# NIRGM_V5.net
KiCad netlist of a schematic drawn in EAGLE
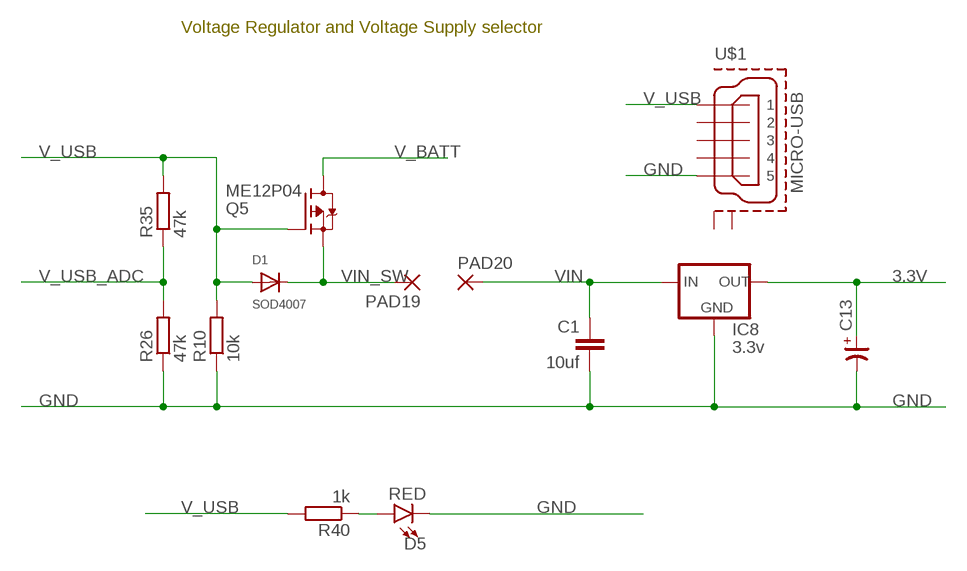
[diagram p0: schematic, sheet 1]
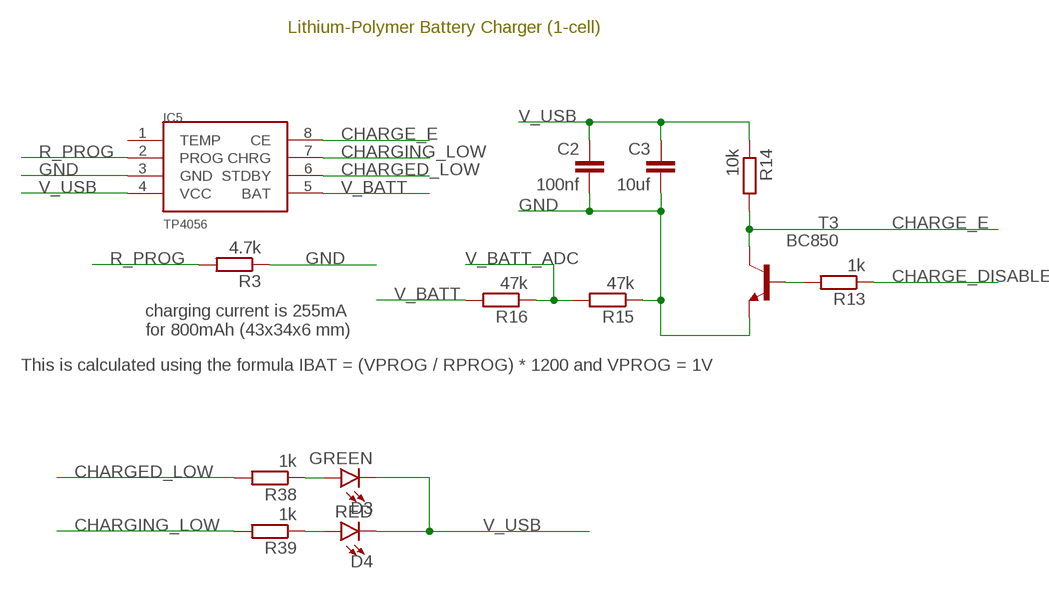
[diagram p1: schematic, sheet 2]
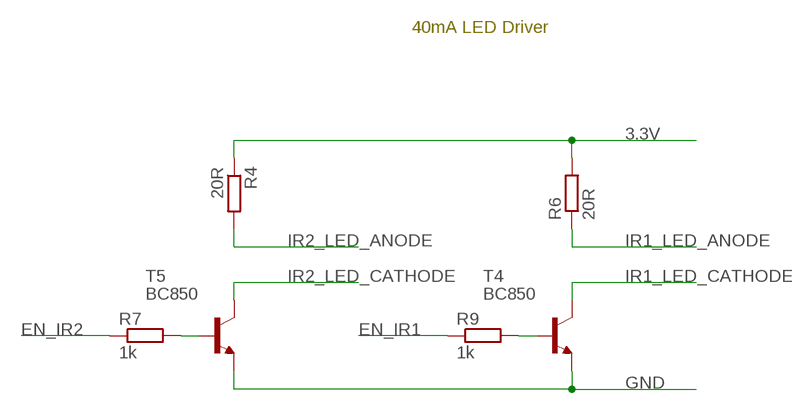
[diagram p2: schematic, sheet 3]
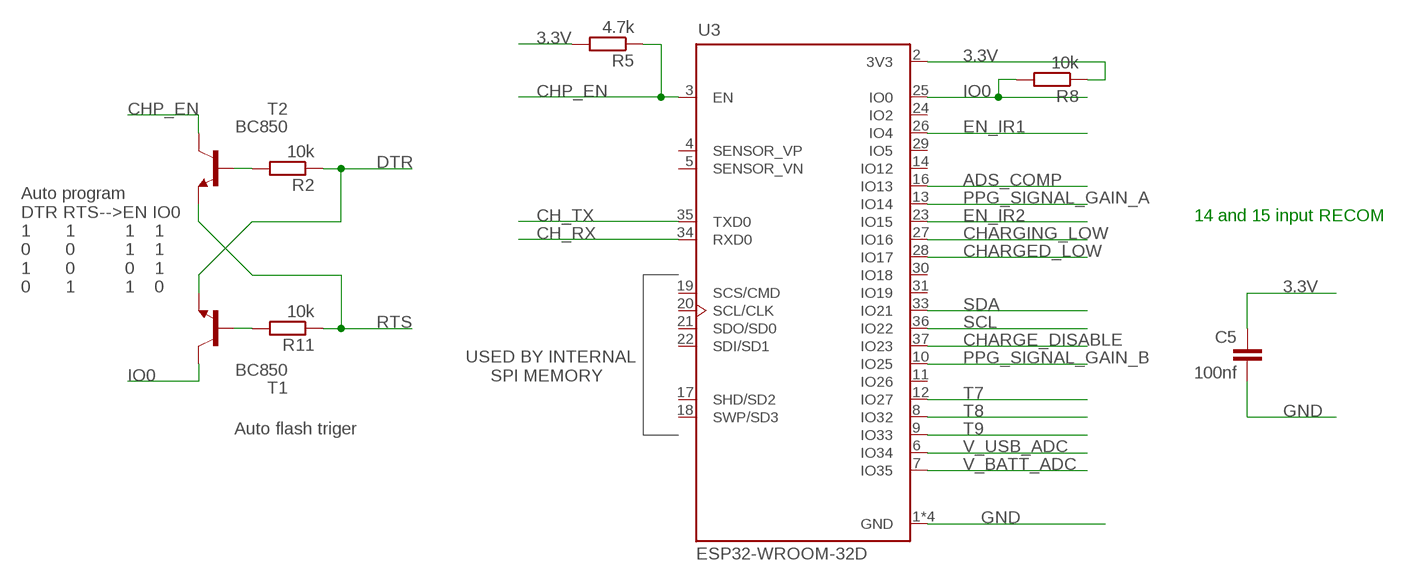
[diagram p3: schematic, sheet 4]
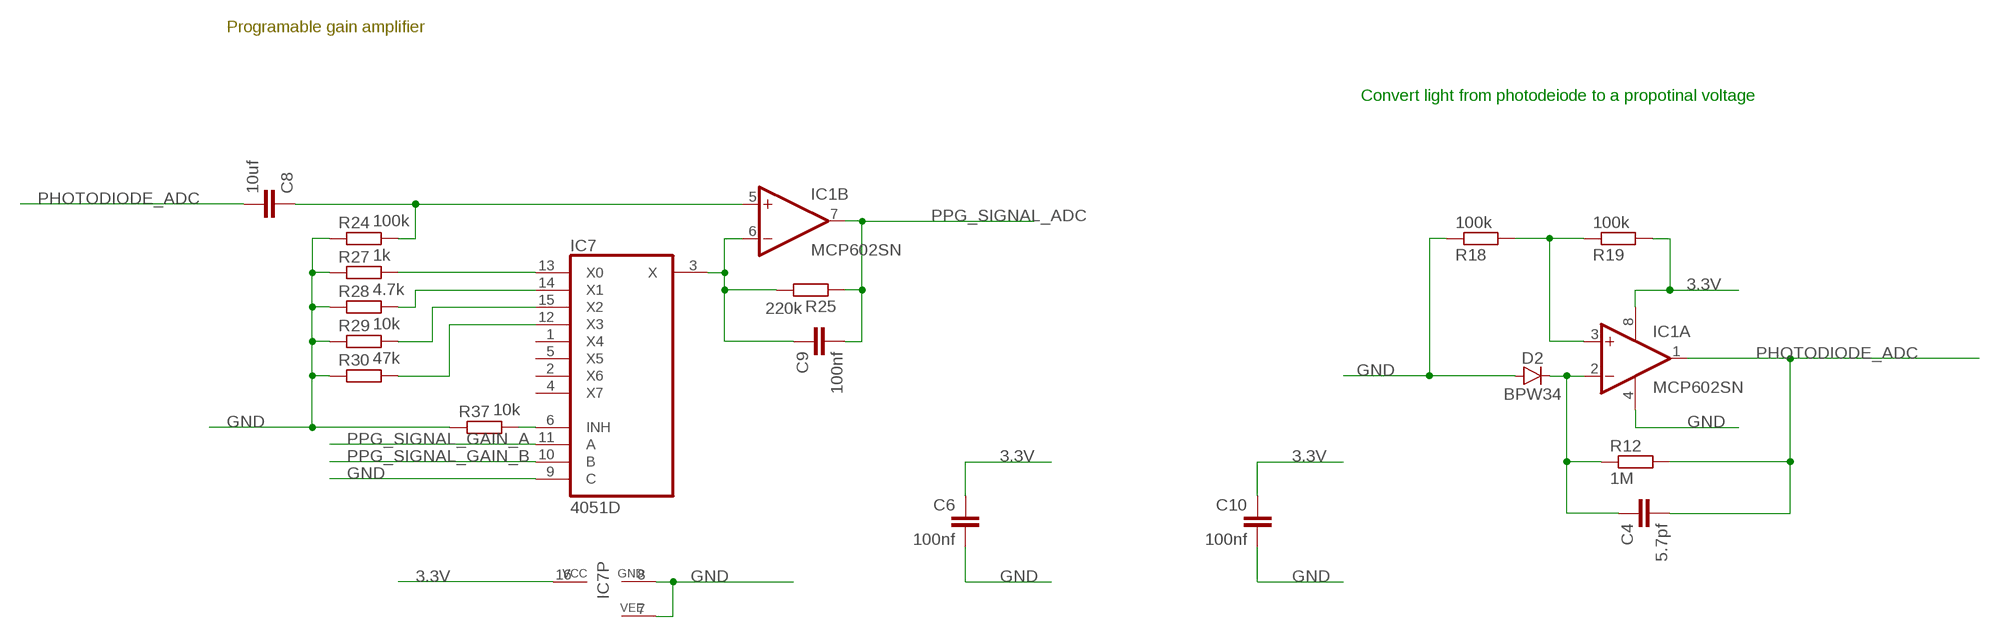
[diagram p4: schematic, sheet 5]
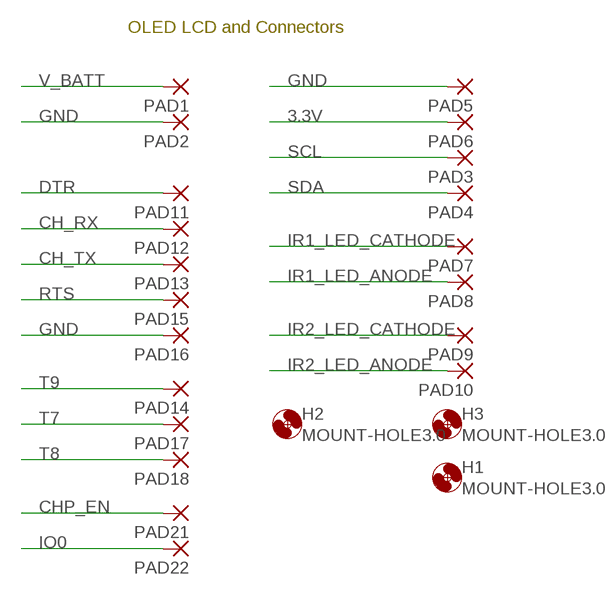
[diagram p5: schematic, sheet 6]
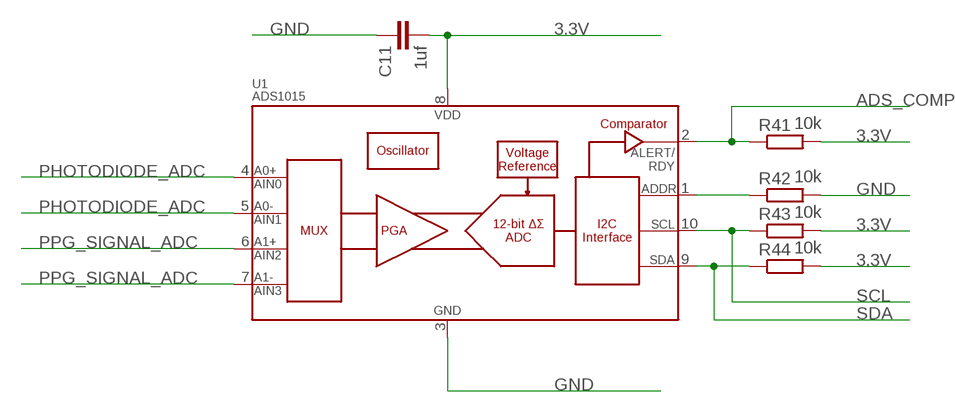
[diagram p6: schematic, sheet 7]

(export (version "E")
  (design (tool "Eeschema 10.0.6"))
  (components
    (comp (ref "C5")
      (value "100nf")
      (footprint "eagle-import:C1206K")
      (libsource (lib "eagle-import") (part "C-EUC1206K"))
    )
    (comp (ref "R2")
      (value "10k")
      (footprint "eagle-import:R1206")
      (libsource (lib "eagle-import") (part "R-EU_R1206"))
    )
    (comp (ref "R5")
      (value "4.7k")
      (footprint "eagle-import:R1206")
      (libsource (lib "eagle-import") (part "R-EU_R1206"))
    )
    (comp (ref "R8")
      (value "10k")
      (footprint "eagle-import:R1206")
      (libsource (lib "eagle-import") (part "R-EU_R1206"))
    )
    (comp (ref "R11")
      (value "10k")
      (footprint "eagle-import:R1206")
      (libsource (lib "eagle-import") (part "R-EU_R1206"))
    )
    (comp (ref "T1")
      (value "BC850")
      (footprint "eagle-import:SOT23")
      (libsource (lib "eagle-import") (part "BC850"))
    )
    (comp (ref "T2")
      (value "BC850")
      (footprint "eagle-import:SOT23")
      (libsource (lib "eagle-import") (part "BC850"))
    )
    (comp (ref "U3")
      (value "ESP32-WROOM-32D")
      (footprint "eagle-import:MODULE_ESP32-WROOM-32D")
      (fields (field (name "MF") "Espressif Systems"))
      (libsource (lib "eagle-import") (part "ESP32-WROOM-32D"))
    )
    (comp (ref "C11")
      (value "1uf")
      (footprint "eagle-import:C1206K")
      (libsource (lib "eagle-import") (part "C-EUC1206K"))
    )
    (comp (ref "R41")
      (value "10k")
      (footprint "eagle-import:R1206")
      (libsource (lib "eagle-import") (part "R-EU_R1206"))
    )
    (comp (ref "R42")
      (value "10k")
      (footprint "eagle-import:R1206")
      (libsource (lib "eagle-import") (part "R-EU_R1206"))
    )
    (comp (ref "R43")
      (value "10k")
      (footprint "eagle-import:R1206")
      (libsource (lib "eagle-import") (part "R-EU_R1206"))
    )
    (comp (ref "R44")
      (value "10k")
      (footprint "eagle-import:R1206")
      (libsource (lib "eagle-import") (part "R-EU_R1206"))
    )
    (comp (ref "U1")
      (value "ADS1015")
      (footprint "eagle-import:MSOP10")
      (libsource (lib "eagle-import") (part "ADS1015"))
    )
    (comp (ref "C2")
      (value "100nf")
      (footprint "eagle-import:C1206K")
      (libsource (lib "eagle-import") (part "C-EUC1206K"))
    )
    (comp (ref "C3")
      (value "10uf")
      (footprint "eagle-import:C1206K")
      (libsource (lib "eagle-import") (part "C-EUC1206K"))
    )
    (comp (ref "D3")
      (value "GREEN")
      (footprint "eagle-import:LED-1206")
      (libsource (lib "eagle-import") (part "LED-GREEN1206"))
    )
    (comp (ref "D4")
      (value "RED")
      (footprint "eagle-import:LED-1206")
      (libsource (lib "eagle-import") (part "LED-GREEN1206"))
    )
    (comp (ref "IC5")
      (value "TP4056")
      (footprint "eagle-import:SOP-8")
      (libsource (lib "eagle-import") (part "TP4056"))
    )
    (comp (ref "R3")
      (value "4.7k")
      (footprint "eagle-import:R1206")
      (libsource (lib "eagle-import") (part "R-EU_R1206"))
    )
    (comp (ref "R13")
      (value "1k")
      (footprint "eagle-import:R1206")
      (libsource (lib "eagle-import") (part "R-EU_R1206"))
    )
    (comp (ref "R14")
      (value "10k")
      (footprint "eagle-import:R1206")
      (libsource (lib "eagle-import") (part "R-EU_R1206"))
    )
    (comp (ref "R15")
      (value "47k")
      (footprint "eagle-import:R1206")
      (libsource (lib "eagle-import") (part "R-EU_R1206"))
    )
    (comp (ref "R16")
      (value "47k")
      (footprint "eagle-import:R1206")
      (libsource (lib "eagle-import") (part "R-EU_R1206"))
    )
    (comp (ref "R38")
      (value "1k")
      (footprint "eagle-import:R1206")
      (libsource (lib "eagle-import") (part "R-EU_R1206"))
    )
    (comp (ref "R39")
      (value "1k")
      (footprint "eagle-import:R1206")
      (libsource (lib "eagle-import") (part "R-EU_R1206"))
    )
    (comp (ref "T3")
      (value "BC850")
      (footprint "eagle-import:SOT23")
      (libsource (lib "eagle-import") (part "BC850"))
    )
    (comp (ref "R4")
      (value "20R")
      (footprint "eagle-import:R1206")
      (libsource (lib "eagle-import") (part "R-EU_R1206"))
    )
    (comp (ref "R6")
      (value "20R")
      (footprint "eagle-import:R1206")
      (libsource (lib "eagle-import") (part "R-EU_R1206"))
    )
    (comp (ref "R7")
      (value "1k")
      (footprint "eagle-import:R1206")
      (libsource (lib "eagle-import") (part "R-EU_R1206"))
    )
    (comp (ref "R9")
      (value "1k")
      (footprint "eagle-import:R1206")
      (libsource (lib "eagle-import") (part "R-EU_R1206"))
    )
    (comp (ref "T4")
      (value "BC850")
      (footprint "eagle-import:SOT23")
      (libsource (lib "eagle-import") (part "BC850"))
    )
    (comp (ref "T5")
      (value "BC850")
      (footprint "eagle-import:SOT23")
      (libsource (lib "eagle-import") (part "BC850"))
    )
    (comp (ref "C1")
      (value "10uf")
      (footprint "eagle-import:C1206K")
      (libsource (lib "eagle-import") (part "C-EUC1206K"))
    )
    (comp (ref "C13")
      (value "CP-7343")
      (footprint "eagle-import:7343_T")
      (libsource (lib "eagle-import") (part "CP-7343"))
    )
    (comp (ref "D1")
      (value "SOD4007")
      (footprint "eagle-import:SOD-123FL")
      (libsource (lib "eagle-import") (part "DIODE_SOD-123FL"))
    )
    (comp (ref "D5")
      (value "RED")
      (footprint "eagle-import:LED-1206")
      (libsource (lib "eagle-import") (part "LED-GREEN1206"))
    )
    (comp (ref "IC8")
      (value "3.3v")
      (footprint "eagle-import:TO252")
      (libsource (lib "eagle-import") (part "LM1117TO252"))
    )
    (comp (ref "PAD19")
      (value "SMD2")
      (footprint "eagle-import:SMD1,27-2,54")
      (libsource (lib "eagle-import") (part "SMD2"))
    )
    (comp (ref "PAD20")
      (value "SMD2")
      (footprint "eagle-import:SMD1,27-2,54")
      (libsource (lib "eagle-import") (part "SMD2"))
    )
    (comp (ref "Q5")
      (value "ME12P04")
      (footprint "eagle-import:TO252")
      (libsource (lib "eagle-import") (part "FDD4141TO252"))
    )
    (comp (ref "R10")
      (value "10k")
      (footprint "eagle-import:R1206")
      (libsource (lib "eagle-import") (part "R-EU_R1206"))
    )
    (comp (ref "R26")
      (value "47k")
      (footprint "eagle-import:R1206")
      (libsource (lib "eagle-import") (part "R-EU_R1206"))
    )
    (comp (ref "R35")
      (value "47k")
      (footprint "eagle-import:R1206")
      (libsource (lib "eagle-import") (part "R-EU_R1206"))
    )
    (comp (ref "R40")
      (value "1k")
      (footprint "eagle-import:R1206")
      (libsource (lib "eagle-import") (part "R-EU_R1206"))
    )
    (comp (ref "U$1")
      (value "MICRO-USB")
      (footprint "eagle-import:47589-0001")
      (libsource (lib "eagle-import") (part "MICRO-USB-RECEPTACLE47589-0001"))
    )
    (comp (ref "H1")
      (value "MOUNT-HOLE3.0")
      (footprint "eagle-import:3,0")
      (libsource (lib "eagle-import") (part "MOUNT-HOLE3.0"))
    )
    (comp (ref "H2")
      (value "MOUNT-HOLE3.0")
      (footprint "eagle-import:3,0")
      (libsource (lib "eagle-import") (part "MOUNT-HOLE3.0"))
    )
    (comp (ref "H3")
      (value "MOUNT-HOLE3.0")
      (footprint "eagle-import:3,0")
      (libsource (lib "eagle-import") (part "MOUNT-HOLE3.0"))
    )
    (comp (ref "PAD1")
      (value "WIREPADSMD5-2,5")
      (footprint "eagle-import:5-2,5")
      (libsource (lib "eagle-import") (part "WIREPADSMD5-2,5"))
    )
    (comp (ref "PAD2")
      (value "WIREPADSMD5-2,5")
      (footprint "eagle-import:5-2,5")
      (libsource (lib "eagle-import") (part "WIREPADSMD5-2,5"))
    )
    (comp (ref "PAD3")
      (value "SMD2")
      (footprint "eagle-import:SMD1,27-2,54")
      (libsource (lib "eagle-import") (part "SMD2"))
    )
    (comp (ref "PAD4")
      (value "SMD2")
      (footprint "eagle-import:SMD1,27-2,54")
      (libsource (lib "eagle-import") (part "SMD2"))
    )
    (comp (ref "PAD5")
      (value "SMD2")
      (footprint "eagle-import:SMD1,27-2,54")
      (libsource (lib "eagle-import") (part "SMD2"))
    )
    (comp (ref "PAD6")
      (value "SMD2")
      (footprint "eagle-import:SMD1,27-2,54")
      (libsource (lib "eagle-import") (part "SMD2"))
    )
    (comp (ref "PAD7")
      (value "SMD2")
      (footprint "eagle-import:SMD1,27-2,54")
      (libsource (lib "eagle-import") (part "SMD2"))
    )
    (comp (ref "PAD8")
      (value "SMD2")
      (footprint "eagle-import:SMD1,27-2,54")
      (libsource (lib "eagle-import") (part "SMD2"))
    )
    (comp (ref "PAD9")
      (value "SMD2")
      (footprint "eagle-import:SMD1,27-2,54")
      (libsource (lib "eagle-import") (part "SMD2"))
    )
    (comp (ref "PAD10")
      (value "SMD2")
      (footprint "eagle-import:SMD1,27-2,54")
      (libsource (lib "eagle-import") (part "SMD2"))
    )
    (comp (ref "PAD11")
      (value "SMD2")
      (footprint "eagle-import:SMD1,27-2,54")
      (libsource (lib "eagle-import") (part "SMD2"))
    )
    (comp (ref "PAD12")
      (value "SMD2")
      (footprint "eagle-import:SMD1,27-2,54")
      (libsource (lib "eagle-import") (part "SMD2"))
    )
    (comp (ref "PAD13")
      (value "SMD2")
      (footprint "eagle-import:SMD1,27-2,54")
      (libsource (lib "eagle-import") (part "SMD2"))
    )
    (comp (ref "PAD14")
      (value "SMD2")
      (footprint "eagle-import:SMD1,27-2,54")
      (libsource (lib "eagle-import") (part "SMD2"))
    )
    (comp (ref "PAD15")
      (value "SMD2")
      (footprint "eagle-import:SMD1,27-2,54")
      (libsource (lib "eagle-import") (part "SMD2"))
    )
    (comp (ref "PAD16")
      (value "SMD2")
      (footprint "eagle-import:SMD1,27-2,54")
      (libsource (lib "eagle-import") (part "SMD2"))
    )
    (comp (ref "PAD17")
      (value "SMD2")
      (footprint "eagle-import:SMD1,27-2,54")
      (libsource (lib "eagle-import") (part "SMD2"))
    )
    (comp (ref "PAD18")
      (value "SMD2")
      (footprint "eagle-import:SMD1,27-2,54")
      (libsource (lib "eagle-import") (part "SMD2"))
    )
    (comp (ref "PAD21")
      (value "SMD2")
      (footprint "eagle-import:SMD1,27-2,54")
      (libsource (lib "eagle-import") (part "SMD2"))
    )
    (comp (ref "PAD22")
      (value "SMD2")
      (footprint "eagle-import:SMD1,27-2,54")
      (libsource (lib "eagle-import") (part "SMD2"))
    )
    (comp (ref "C4")
      (value "5.7pf")
      (footprint "eagle-import:C1206K")
      (libsource (lib "eagle-import") (part "C-EUC1206K"))
    )
    (comp (ref "C6")
      (value "100nf")
      (footprint "eagle-import:C1206K")
      (libsource (lib "eagle-import") (part "C-EUC1206K"))
    )
    (comp (ref "C8")
      (value "10uf")
      (footprint "eagle-import:C1206K")
      (libsource (lib "eagle-import") (part "C-EUC1206K"))
    )
    (comp (ref "C9")
      (value "100nf")
      (footprint "eagle-import:C1206K")
      (libsource (lib "eagle-import") (part "C-EUC1206K"))
    )
    (comp (ref "C10")
      (value "100nf")
      (footprint "eagle-import:C1206K")
      (libsource (lib "eagle-import") (part "C-EUC1206K"))
    )
    (comp (ref "D2")
      (value "BPW34")
      (footprint "eagle-import:BPW34")
      (libsource (lib "eagle-import") (part "BPW34"))
    )
    (comp (ref "IC1")
      (value "MCP602SN")
      (footprint "eagle-import:SO08")
      (libsource (lib "eagle-import") (part "MCP602SN"))
    )
    (comp (ref "IC7")
      (value "4051D")
      (footprint "eagle-import:SO16")
      (libsource (lib "eagle-import") (part "4051D"))
    )
    (comp (ref "R12")
      (value "1M")
      (footprint "eagle-import:R1206")
      (libsource (lib "eagle-import") (part "R-EU_R1206"))
    )
    (comp (ref "R18")
      (value "100k")
      (footprint "eagle-import:R1206")
      (libsource (lib "eagle-import") (part "R-EU_R1206"))
    )
    (comp (ref "R19")
      (value "100k")
      (footprint "eagle-import:R1206")
      (libsource (lib "eagle-import") (part "R-EU_R1206"))
    )
    (comp (ref "R24")
      (value "100k")
      (footprint "eagle-import:R1206")
      (libsource (lib "eagle-import") (part "R-EU_R1206"))
    )
    (comp (ref "R25")
      (value "220k")
      (footprint "eagle-import:R1206")
      (libsource (lib "eagle-import") (part "R-EU_R1206"))
    )
    (comp (ref "R27")
      (value "1k")
      (footprint "eagle-import:R1206")
      (libsource (lib "eagle-import") (part "R-EU_R1206"))
    )
    (comp (ref "R28")
      (value "4.7k")
      (footprint "eagle-import:R1206")
      (libsource (lib "eagle-import") (part "R-EU_R1206"))
    )
    (comp (ref "R29")
      (value "10k")
      (footprint "eagle-import:R1206")
      (libsource (lib "eagle-import") (part "R-EU_R1206"))
    )
    (comp (ref "R30")
      (value "47k")
      (footprint "eagle-import:R1206")
      (libsource (lib "eagle-import") (part "R-EU_R1206"))
    )
    (comp (ref "R37")
      (value "10k")
      (footprint "eagle-import:R1206")
      (libsource (lib "eagle-import") (part "R-EU_R1206"))
    )
  )
  (nets
    (net (code "1") (name "3.3V") (class "Default")
      (node (ref "C10") (pin "1") (pinfunction "1_1") (pintype "passive"))
      (node (ref "C11") (pin "2") (pinfunction "2_2") (pintype "passive"))
      (node (ref "C13") (pin "+") (pinfunction "+_+") (pintype "passive"))
      (node (ref "C5") (pin "1") (pinfunction "1_1") (pintype "passive"))
      (node (ref "C6") (pin "1") (pinfunction "1_1") (pintype "passive"))
      (node (ref "IC1") (pin "8") (pinfunction "V+_8") (pintype "power_in"))
      (node (ref "IC7") (pin "16") (pinfunction "VCC_16") (pintype "power_in"))
      (node (ref "IC8") (pin "3") (pinfunction "OUT_3") (pintype "passive"))
      (node (ref "PAD6") (pin "1") (pinfunction "P_1") (pintype "passive"))
      (node (ref "R19") (pin "2") (pinfunction "2_2") (pintype "passive"))
      (node (ref "R4") (pin "1") (pinfunction "1_1") (pintype "passive"))
      (node (ref "R41") (pin "2") (pinfunction "2_2") (pintype "passive"))
      (node (ref "R43") (pin "2") (pinfunction "2_2") (pintype "passive"))
      (node (ref "R44") (pin "2") (pinfunction "2_2") (pintype "passive"))
      (node (ref "R5") (pin "2") (pinfunction "2_2") (pintype "passive"))
      (node (ref "R6") (pin "2") (pinfunction "2_2") (pintype "passive"))
      (node (ref "R8") (pin "1") (pinfunction "1_1") (pintype "passive"))
      (node (ref "U1") (pin "8") (pinfunction "VDD_8") (pintype "bidirectional"))
      (node (ref "U3") (pin "2") (pinfunction "3V3_2") (pintype "power_in"))
    )
    (net (code "2") (name "ADS_COMP") (class "Default")
      (node (ref "R41") (pin "1") (pinfunction "1_1") (pintype "passive"))
      (node (ref "U1") (pin "2") (pinfunction "ALERT/RDY_2") (pintype "bidirectional"))
      (node (ref "U3") (pin "16") (pinfunction "IO13_16") (pintype "bidirectional"))
    )
    (net (code "3") (name "CHARGED_LOW") (class "Default")
      (node (ref "IC5") (pin "6") (pinfunction "STDBY_6") (pintype "bidirectional"))
      (node (ref "R38") (pin "2") (pinfunction "2_2") (pintype "passive"))
      (node (ref "U3") (pin "28") (pinfunction "IO17_28") (pintype "bidirectional"))
    )
    (net (code "4") (name "CHARGE_DISABLE") (class "Default")
      (node (ref "R13") (pin "1") (pinfunction "1_1") (pintype "passive"))
      (node (ref "U3") (pin "37") (pinfunction "IO23_37") (pintype "bidirectional"))
    )
    (net (code "5") (name "CHARGE_E") (class "Default")
      (node (ref "IC5") (pin "8") (pinfunction "CE_8") (pintype "bidirectional"))
      (node (ref "R14") (pin "2") (pinfunction "2_2") (pintype "passive"))
      (node (ref "T3") (pin "3") (pinfunction "C_3") (pintype "passive"))
    )
    (net (code "6") (name "CHARGING_LOW") (class "Default")
      (node (ref "IC5") (pin "7") (pinfunction "CHRG_7") (pintype "bidirectional"))
      (node (ref "R39") (pin "2") (pinfunction "2_2") (pintype "passive"))
      (node (ref "U3") (pin "27") (pinfunction "IO16_27") (pintype "bidirectional"))
    )
    (net (code "7") (name "CHP_EN") (class "Default")
      (node (ref "PAD21") (pin "1") (pinfunction "P_1") (pintype "passive"))
      (node (ref "R5") (pin "1") (pinfunction "1_1") (pintype "passive"))
      (node (ref "T2") (pin "3") (pinfunction "C_3") (pintype "passive"))
      (node (ref "U3") (pin "3") (pinfunction "EN_3") (pintype "input"))
    )
    (net (code "8") (name "CH_RX") (class "Default")
      (node (ref "PAD12") (pin "1") (pinfunction "P_1") (pintype "passive"))
      (node (ref "U3") (pin "34") (pinfunction "RXD0_34") (pintype "bidirectional"))
    )
    (net (code "9") (name "CH_TX") (class "Default")
      (node (ref "PAD13") (pin "1") (pinfunction "P_1") (pintype "passive"))
      (node (ref "U3") (pin "35") (pinfunction "TXD0_35") (pintype "bidirectional"))
    )
    (net (code "10") (name "DTR") (class "Default")
      (node (ref "PAD11") (pin "1") (pinfunction "P_1") (pintype "passive"))
      (node (ref "R2") (pin "1") (pinfunction "1_1") (pintype "passive"))
      (node (ref "T1") (pin "2") (pinfunction "E_2") (pintype "passive"))
    )
    (net (code "11") (name "EN_IR1") (class "Default")
      (node (ref "R9") (pin "1") (pinfunction "1_1") (pintype "passive"))
      (node (ref "U3") (pin "26") (pinfunction "IO4_26") (pintype "bidirectional"))
    )
    (net (code "12") (name "EN_IR2") (class "Default")
      (node (ref "R7") (pin "1") (pinfunction "1_1") (pintype "passive"))
      (node (ref "U3") (pin "23") (pinfunction "IO15_23") (pintype "bidirectional"))
    )
    (net (code "13") (name "GND") (class "Default")
      (node (ref "C1") (pin "2") (pinfunction "2_2") (pintype "passive"))
      (node (ref "C10") (pin "2") (pinfunction "2_2") (pintype "passive"))
      (node (ref "C11") (pin "1") (pinfunction "1_1") (pintype "passive"))
      (node (ref "C13") (pin "-") (pinfunction "-_-") (pintype "passive"))
      (node (ref "C2") (pin "2") (pinfunction "2_2") (pintype "passive"))
      (node (ref "C3") (pin "2") (pinfunction "2_2") (pintype "passive"))
      (node (ref "C5") (pin "2") (pinfunction "2_2") (pintype "passive"))
      (node (ref "C6") (pin "2") (pinfunction "2_2") (pintype "passive"))
      (node (ref "D2") (pin "P$1") (pinfunction "A_P$1") (pintype "passive"))
      (node (ref "D5") (pin "C") (pinfunction "C_C") (pintype "passive"))
      (node (ref "IC1") (pin "4") (pinfunction "V-_4") (pintype "power_in"))
      (node (ref "IC5") (pin "3") (pinfunction "GND_3") (pintype "bidirectional"))
      (node (ref "IC7") (pin "7") (pinfunction "VEE_7") (pintype "power_in"))
      (node (ref "IC7") (pin "8") (pinfunction "GND_8") (pintype "power_in"))
      (node (ref "IC7") (pin "9") (pinfunction "C_9") (pintype "input"))
      (node (ref "IC8") (pin "1") (pinfunction "GND_1") (pintype "input"))
      (node (ref "PAD16") (pin "1") (pinfunction "P_1") (pintype "passive"))
      (node (ref "PAD2") (pin "1") (pinfunction "P_1") (pintype "passive"))
      (node (ref "PAD5") (pin "1") (pinfunction "P_1") (pintype "passive"))
      (node (ref "R10") (pin "1") (pinfunction "1_1") (pintype "passive"))
      (node (ref "R15") (pin "1") (pinfunction "1_1") (pintype "passive"))
      (node (ref "R18") (pin "1") (pinfunction "1_1") (pintype "passive"))
      (node (ref "R24") (pin "1") (pinfunction "1_1") (pintype "passive"))
      (node (ref "R26") (pin "1") (pinfunction "1_1") (pintype "passive"))
      (node (ref "R27") (pin "1") (pinfunction "1_1") (pintype "passive"))
      (node (ref "R28") (pin "1") (pinfunction "1_1") (pintype "passive"))
      (node (ref "R29") (pin "1") (pinfunction "1_1") (pintype "passive"))
      (node (ref "R3") (pin "1") (pinfunction "1_1") (pintype "passive"))
      (node (ref "R30") (pin "1") (pinfunction "1_1") (pintype "passive"))
      (node (ref "R37") (pin "1") (pinfunction "1_1") (pintype "passive"))
      (node (ref "R42") (pin "2") (pinfunction "2_2") (pintype "passive"))
      (node (ref "T3") (pin "2") (pinfunction "E_2") (pintype "passive"))
      (node (ref "T4") (pin "2") (pinfunction "E_2") (pintype "passive"))
      (node (ref "T5") (pin "2") (pinfunction "E_2") (pintype "passive"))
      (node (ref "U$1") (pin "5") (pinfunction "5_5") (pintype "input"))
      (node (ref "U1") (pin "3") (pinfunction "VSS_3") (pintype "bidirectional"))
      (node (ref "U3") (pin "1") (pinfunction "GND_1") (pintype "power_in"))
      (node (ref "U3") (pin "15") (pinfunction "GND_15") (pintype "power_in"))
      (node (ref "U3") (pin "38") (pinfunction "GND_38") (pintype "power_in"))
      (node (ref "U3") (pin "39") (pinfunction "GND_39") (pintype "power_in"))
    )
    (net (code "14") (name "IO0") (class "Default")
      (node (ref "PAD22") (pin "1") (pinfunction "P_1") (pintype "passive"))
      (node (ref "R8") (pin "2") (pinfunction "2_2") (pintype "passive"))
      (node (ref "T1") (pin "3") (pinfunction "C_3") (pintype "passive"))
      (node (ref "U3") (pin "25") (pinfunction "IO0_25") (pintype "bidirectional"))
    )
    (net (code "15") (name "IR1_LED_ANODE") (class "Default")
      (node (ref "PAD8") (pin "1") (pinfunction "P_1") (pintype "passive"))
      (node (ref "R6") (pin "1") (pinfunction "1_1") (pintype "passive"))
    )
    (net (code "16") (name "IR1_LED_CATHODE") (class "Default")
      (node (ref "PAD7") (pin "1") (pinfunction "P_1") (pintype "passive"))
      (node (ref "T4") (pin "3") (pinfunction "C_3") (pintype "passive"))
    )
    (net (code "17") (name "IR2_LED_ANODE") (class "Default")
      (node (ref "PAD10") (pin "1") (pinfunction "P_1") (pintype "passive"))
      (node (ref "R4") (pin "2") (pinfunction "2_2") (pintype "passive"))
    )
    (net (code "18") (name "IR2_LED_CATHODE") (class "Default")
      (node (ref "PAD9") (pin "1") (pinfunction "P_1") (pintype "passive"))
      (node (ref "T5") (pin "3") (pinfunction "C_3") (pintype "passive"))
    )
    (net (code "19") (name "Net-(D2-C)") (class "Default")
      (node (ref "C4") (pin "1") (pinfunction "1_1") (pintype "passive"))
      (node (ref "D2") (pin "P$2") (pinfunction "C_P$2") (pintype "passive"))
      (node (ref "IC1") (pin "2") (pinfunction "-IN_2") (pintype "input"))
      (node (ref "R12") (pin "1") (pinfunction "1_1") (pintype "passive"))
    )
    (net (code "20") (name "Net-(D3-PadA)") (class "Default")
      (node (ref "D3") (pin "A") (pinfunction "A_A") (pintype "passive"))
      (node (ref "R38") (pin "1") (pinfunction "1_1") (pintype "passive"))
    )
    (net (code "21") (name "Net-(D4-PadA)") (class "Default")
      (node (ref "D4") (pin "A") (pinfunction "A_A") (pintype "passive"))
      (node (ref "R39") (pin "1") (pinfunction "1_1") (pintype "passive"))
    )
    (net (code "22") (name "Net-(D5-PadA)") (class "Default")
      (node (ref "D5") (pin "A") (pinfunction "A_A") (pintype "passive"))
      (node (ref "R40") (pin "1") (pinfunction "1_1") (pintype "passive"))
    )
    (net (code "23") (name "Net-(IC1A-+IN)") (class "Default")
      (node (ref "IC1") (pin "3") (pinfunction "+IN_3") (pintype "input"))
      (node (ref "R18") (pin "2") (pinfunction "2_2") (pintype "passive"))
      (node (ref "R19") (pin "1") (pinfunction "1_1") (pintype "passive"))
    )
    (net (code "24") (name "Net-(IC1B-+IN)") (class "Default")
      (node (ref "C8") (pin "1") (pinfunction "1_1") (pintype "passive"))
      (node (ref "IC1") (pin "5") (pinfunction "+IN_5") (pintype "input"))
      (node (ref "R24") (pin "2") (pinfunction "2_2") (pintype "passive"))
    )
    (net (code "25") (name "Net-(IC1B--IN)") (class "Default")
      (node (ref "C9") (pin "1") (pinfunction "1_1") (pintype "passive"))
      (node (ref "IC1") (pin "6") (pinfunction "-IN_6") (pintype "input"))
      (node (ref "IC7") (pin "3") (pinfunction "X_3") (pintype "bidirectional"))
      (node (ref "R25") (pin "2") (pinfunction "2_2") (pintype "passive"))
    )
    (net (code "26") (name "Net-(IC7A-INH)") (class "Default")
      (node (ref "IC7") (pin "6") (pinfunction "INH_6") (pintype "input"))
      (node (ref "R37") (pin "2") (pinfunction "2_2") (pintype "passive"))
    )
    (net (code "27") (name "Net-(IC7A-X0)") (class "Default")
      (node (ref "IC7") (pin "13") (pinfunction "X0_13") (pintype "bidirectional"))
      (node (ref "R27") (pin "2") (pinfunction "2_2") (pintype "passive"))
    )
    (net (code "28") (name "Net-(IC7A-X1)") (class "Default")
      (node (ref "IC7") (pin "14") (pinfunction "X1_14") (pintype "bidirectional"))
      (node (ref "R28") (pin "2") (pinfunction "2_2") (pintype "passive"))
    )
    (net (code "29") (name "Net-(IC7A-X2)") (class "Default")
      (node (ref "IC7") (pin "15") (pinfunction "X2_15") (pintype "bidirectional"))
      (node (ref "R29") (pin "2") (pinfunction "2_2") (pintype "passive"))
    )
    (net (code "30") (name "Net-(IC7A-X3)") (class "Default")
      (node (ref "IC7") (pin "12") (pinfunction "X3_12") (pintype "bidirectional"))
      (node (ref "R30") (pin "2") (pinfunction "2_2") (pintype "passive"))
    )
    (net (code "31") (name "Net-(T1-B)") (class "Default")
      (node (ref "R11") (pin "2") (pinfunction "2_2") (pintype "passive"))
      (node (ref "T1") (pin "1") (pinfunction "B_1") (pintype "passive"))
    )
    (net (code "32") (name "Net-(T2-B)") (class "Default")
      (node (ref "R2") (pin "2") (pinfunction "2_2") (pintype "passive"))
      (node (ref "T2") (pin "1") (pinfunction "B_1") (pintype "passive"))
    )
    (net (code "33") (name "Net-(T3-B)") (class "Default")
      (node (ref "R13") (pin "2") (pinfunction "2_2") (pintype "passive"))
      (node (ref "T3") (pin "1") (pinfunction "B_1") (pintype "passive"))
    )
    (net (code "34") (name "Net-(T4-B)") (class "Default")
      (node (ref "R9") (pin "2") (pinfunction "2_2") (pintype "passive"))
      (node (ref "T4") (pin "1") (pinfunction "B_1") (pintype "passive"))
    )
    (net (code "35") (name "Net-(T5-B)") (class "Default")
      (node (ref "R7") (pin "2") (pinfunction "2_2") (pintype "passive"))
      (node (ref "T5") (pin "1") (pinfunction "B_1") (pintype "passive"))
    )
    (net (code "36") (name "Net-(U1-ADDR)") (class "Default")
      (node (ref "R42") (pin "1") (pinfunction "1_1") (pintype "passive"))
      (node (ref "U1") (pin "1") (pinfunction "ADDR_1") (pintype "bidirectional"))
    )
    (net (code "37") (name "PHOTODIODE_ADC") (class "Default")
      (node (ref "C4") (pin "2") (pinfunction "2_2") (pintype "passive"))
      (node (ref "C8") (pin "2") (pinfunction "2_2") (pintype "passive"))
      (node (ref "IC1") (pin "1") (pinfunction "OUT_1") (pintype "output"))
      (node (ref "R12") (pin "2") (pinfunction "2_2") (pintype "passive"))
      (node (ref "U1") (pin "4") (pinfunction "AIN0_4") (pintype "bidirectional"))
      (node (ref "U1") (pin "5") (pinfunction "AIN1_5") (pintype "bidirectional"))
    )
    (net (code "38") (name "PPG_SIGNAL_ADC") (class "Default")
      (node (ref "C9") (pin "2") (pinfunction "2_2") (pintype "passive"))
      (node (ref "IC1") (pin "7") (pinfunction "OUT_7") (pintype "output"))
      (node (ref "R25") (pin "1") (pinfunction "1_1") (pintype "passive"))
      (node (ref "U1") (pin "6") (pinfunction "AIN2_6") (pintype "bidirectional"))
      (node (ref "U1") (pin "7") (pinfunction "AIN3_7") (pintype "bidirectional"))
    )
    (net (code "39") (name "PPG_SIGNAL_GAIN_A") (class "Default")
      (node (ref "IC7") (pin "11") (pinfunction "A_11") (pintype "input"))
      (node (ref "U3") (pin "13") (pinfunction "IO14_13") (pintype "bidirectional"))
    )
    (net (code "40") (name "PPG_SIGNAL_GAIN_B") (class "Default")
      (node (ref "IC7") (pin "10") (pinfunction "B_10") (pintype "input"))
      (node (ref "U3") (pin "10") (pinfunction "IO25_10") (pintype "bidirectional"))
    )
    (net (code "41") (name "RTS") (class "Default")
      (node (ref "PAD15") (pin "1") (pinfunction "P_1") (pintype "passive"))
      (node (ref "R11") (pin "1") (pinfunction "1_1") (pintype "passive"))
      (node (ref "T2") (pin "2") (pinfunction "E_2") (pintype "passive"))
    )
    (net (code "42") (name "R_PROG") (class "Default")
      (node (ref "IC5") (pin "2") (pinfunction "PROG_2") (pintype "bidirectional"))
      (node (ref "R3") (pin "2") (pinfunction "2_2") (pintype "passive"))
    )
    (net (code "43") (name "SCL") (class "Default")
      (node (ref "PAD3") (pin "1") (pinfunction "P_1") (pintype "passive"))
      (node (ref "R43") (pin "1") (pinfunction "1_1") (pintype "passive"))
      (node (ref "U1") (pin "10") (pinfunction "SCL_10") (pintype "bidirectional"))
      (node (ref "U3") (pin "36") (pinfunction "IO22_36") (pintype "bidirectional"))
    )
    (net (code "44") (name "SDA") (class "Default")
      (node (ref "PAD4") (pin "1") (pinfunction "P_1") (pintype "passive"))
      (node (ref "R44") (pin "1") (pinfunction "1_1") (pintype "passive"))
      (node (ref "U1") (pin "9") (pinfunction "SDA_9") (pintype "bidirectional"))
      (node (ref "U3") (pin "33") (pinfunction "IO21_33") (pintype "bidirectional"))
    )
    (net (code "45") (name "T7") (class "Default")
      (node (ref "PAD17") (pin "1") (pinfunction "P_1") (pintype "passive"))
      (node (ref "U3") (pin "12") (pinfunction "IO27_12") (pintype "bidirectional"))
    )
    (net (code "46") (name "T8") (class "Default")
      (node (ref "PAD18") (pin "1") (pinfunction "P_1") (pintype "passive"))
      (node (ref "U3") (pin "8") (pinfunction "IO32_8") (pintype "bidirectional"))
    )
    (net (code "47") (name "T9") (class "Default")
      (node (ref "PAD14") (pin "1") (pinfunction "P_1") (pintype "passive"))
      (node (ref "U3") (pin "9") (pinfunction "IO33_9") (pintype "bidirectional"))
    )
    (net (code "48") (name "VIN") (class "Default")
      (node (ref "C1") (pin "1") (pinfunction "1_1") (pintype "passive"))
      (node (ref "IC8") (pin "2") (pinfunction "IN_2") (pintype "input"))
      (node (ref "PAD20") (pin "1") (pinfunction "P_1") (pintype "passive"))
    )
    (net (code "49") (name "VIN_SW") (class "Default")
      (node (ref "D1") (pin "C") (pinfunction "C_C") (pintype "passive"))
      (node (ref "PAD19") (pin "1") (pinfunction "P_1") (pintype "passive"))
      (node (ref "Q5") (pin "2") (pinfunction "S_2") (pintype "passive"))
    )
    (net (code "50") (name "V_BATT") (class "Default")
      (node (ref "IC5") (pin "5") (pinfunction "BAT_5") (pintype "bidirectional"))
      (node (ref "PAD1") (pin "1") (pinfunction "P_1") (pintype "passive"))
      (node (ref "Q5") (pin "3") (pinfunction "D_3") (pintype "passive"))
      (node (ref "R16") (pin "2") (pinfunction "2_2") (pintype "passive"))
    )
    (net (code "51") (name "V_BATT_ADC") (class "Default")
      (node (ref "R15") (pin "2") (pinfunction "2_2") (pintype "passive"))
      (node (ref "R16") (pin "1") (pinfunction "1_1") (pintype "passive"))
      (node (ref "U3") (pin "7") (pinfunction "IO35_7") (pintype "bidirectional"))
    )
    (net (code "52") (name "V_USB") (class "Default")
      (node (ref "C2") (pin "1") (pinfunction "1_1") (pintype "passive"))
      (node (ref "C3") (pin "1") (pinfunction "1_1") (pintype "passive"))
      (node (ref "D1") (pin "A") (pinfunction "A_A") (pintype "passive"))
      (node (ref "D3") (pin "C") (pinfunction "C_C") (pintype "passive"))
      (node (ref "D4") (pin "C") (pinfunction "C_C") (pintype "passive"))
      (node (ref "IC5") (pin "4") (pinfunction "VCC_4") (pintype "bidirectional"))
      (node (ref "Q5") (pin "1") (pinfunction "G_1") (pintype "passive"))
      (node (ref "R10") (pin "2") (pinfunction "2_2") (pintype "passive"))
      (node (ref "R14") (pin "1") (pinfunction "1_1") (pintype "passive"))
      (node (ref "R35") (pin "2") (pinfunction "2_2") (pintype "passive"))
      (node (ref "R40") (pin "2") (pinfunction "2_2") (pintype "passive"))
      (node (ref "U$1") (pin "1") (pinfunction "1_1") (pintype "input"))
    )
    (net (code "53") (name "V_USB_ADC") (class "Default")
      (node (ref "R26") (pin "2") (pinfunction "2_2") (pintype "passive"))
      (node (ref "R35") (pin "1") (pinfunction "1_1") (pintype "passive"))
      (node (ref "U3") (pin "6") (pinfunction "IO34_6") (pintype "bidirectional"))
    )
    (net (code "54") (name "unconnected-(IC5-TEMP-Pad1)") (class "Default")
      (node (ref "IC5") (pin "1") (pinfunction "TEMP_1") (pintype "bidirectional"))
    )
    (net (code "55") (name "unconnected-(IC7A-X4-Pad1)") (class "Default")
      (node (ref "IC7") (pin "1") (pinfunction "X4_1") (pintype "bidirectional"))
    )
    (net (code "56") (name "unconnected-(IC7A-X5-Pad5)") (class "Default")
      (node (ref "IC7") (pin "5") (pinfunction "X5_5") (pintype "bidirectional"))
    )
    (net (code "57") (name "unconnected-(IC7A-X6-Pad2)") (class "Default")
      (node (ref "IC7") (pin "2") (pinfunction "X6_2") (pintype "bidirectional"))
    )
    (net (code "58") (name "unconnected-(IC7A-X7-Pad4)") (class "Default")
      (node (ref "IC7") (pin "4") (pinfunction "X7_4") (pintype "bidirectional"))
    )
    (net (code "59") (name "unconnected-(U$1-GND1-PadP$1)") (class "Default")
      (node (ref "U$1") (pin "P$1") (pinfunction "GND1_P$1") (pintype "bidirectional"))
    )
    (net (code "60") (name "unconnected-(U$1-GND2-PadP$2)") (class "Default")
      (node (ref "U$1") (pin "P$2") (pinfunction "GND2_P$2") (pintype "bidirectional"))
    )
    (net (code "61") (name "unconnected-(U$1-Pad2)") (class "Default")
      (node (ref "U$1") (pin "2") (pinfunction "2_2") (pintype "input"))
    )
    (net (code "62") (name "unconnected-(U$1-Pad3)") (class "Default")
      (node (ref "U$1") (pin "3") (pinfunction "3_3") (pintype "input"))
    )
    (net (code "63") (name "unconnected-(U$1-Pad4)") (class "Default")
      (node (ref "U$1") (pin "4") (pinfunction "4_4") (pintype "input"))
    )
    (net (code "64") (name "unconnected-(U3-IO2-Pad24)") (class "Default")
      (node (ref "U3") (pin "24") (pinfunction "IO2_24") (pintype "bidirectional"))
    )
    (net (code "65") (name "unconnected-(U3-IO5-Pad29)") (class "Default")
      (node (ref "U3") (pin "29") (pinfunction "IO5_29") (pintype "bidirectional"))
    )
    (net (code "66") (name "unconnected-(U3-IO12-Pad14)") (class "Default")
      (node (ref "U3") (pin "14") (pinfunction "IO12_14") (pintype "bidirectional"))
    )
    (net (code "67") (name "unconnected-(U3-IO18-Pad30)") (class "Default")
      (node (ref "U3") (pin "30") (pinfunction "IO18_30") (pintype "bidirectional"))
    )
    (net (code "68") (name "unconnected-(U3-IO19-Pad31)") (class "Default")
      (node (ref "U3") (pin "31") (pinfunction "IO19_31") (pintype "bidirectional"))
    )
    (net (code "69") (name "unconnected-(U3-IO26-Pad11)") (class "Default")
      (node (ref "U3") (pin "11") (pinfunction "IO26_11") (pintype "bidirectional"))
    )
    (net (code "70") (name "unconnected-(U3-SCL{slash}CLK-Pad20)") (class "Default")
      (node (ref "U3") (pin "20") (pinfunction "SCL/CLK_20") (pintype "bidirectional"))
    )
    (net (code "71") (name "unconnected-(U3-SCS{slash}CMD-Pad19)") (class "Default")
      (node (ref "U3") (pin "19") (pinfunction "SCS/CMD_19") (pintype "bidirectional"))
    )
    (net (code "72") (name "unconnected-(U3-SDI{slash}SD1-Pad22)") (class "Default")
      (node (ref "U3") (pin "22") (pinfunction "SDI/SD1_22") (pintype "bidirectional"))
    )
    (net (code "73") (name "unconnected-(U3-SDO{slash}SD0-Pad21)") (class "Default")
      (node (ref "U3") (pin "21") (pinfunction "SDO/SD0_21") (pintype "bidirectional"))
    )
    (net (code "74") (name "unconnected-(U3-SENSOR_VN-Pad5)") (class "Default")
      (node (ref "U3") (pin "5") (pinfunction "SENSOR_VN_5") (pintype "input"))
    )
    (net (code "75") (name "unconnected-(U3-SENSOR_VP-Pad4)") (class "Default")
      (node (ref "U3") (pin "4") (pinfunction "SENSOR_VP_4") (pintype "input"))
    )
    (net (code "76") (name "unconnected-(U3-SHD{slash}SD2-Pad17)") (class "Default")
      (node (ref "U3") (pin "17") (pinfunction "SHD/SD2_17") (pintype "bidirectional"))
    )
    (net (code "77") (name "unconnected-(U3-SWP{slash}SD3-Pad18)") (class "Default")
      (node (ref "U3") (pin "18") (pinfunction "SWP/SD3_18") (pintype "bidirectional"))
    )
  )
)
